# Main.net
KiCad netlist of a schematic drawn in Altium Designer
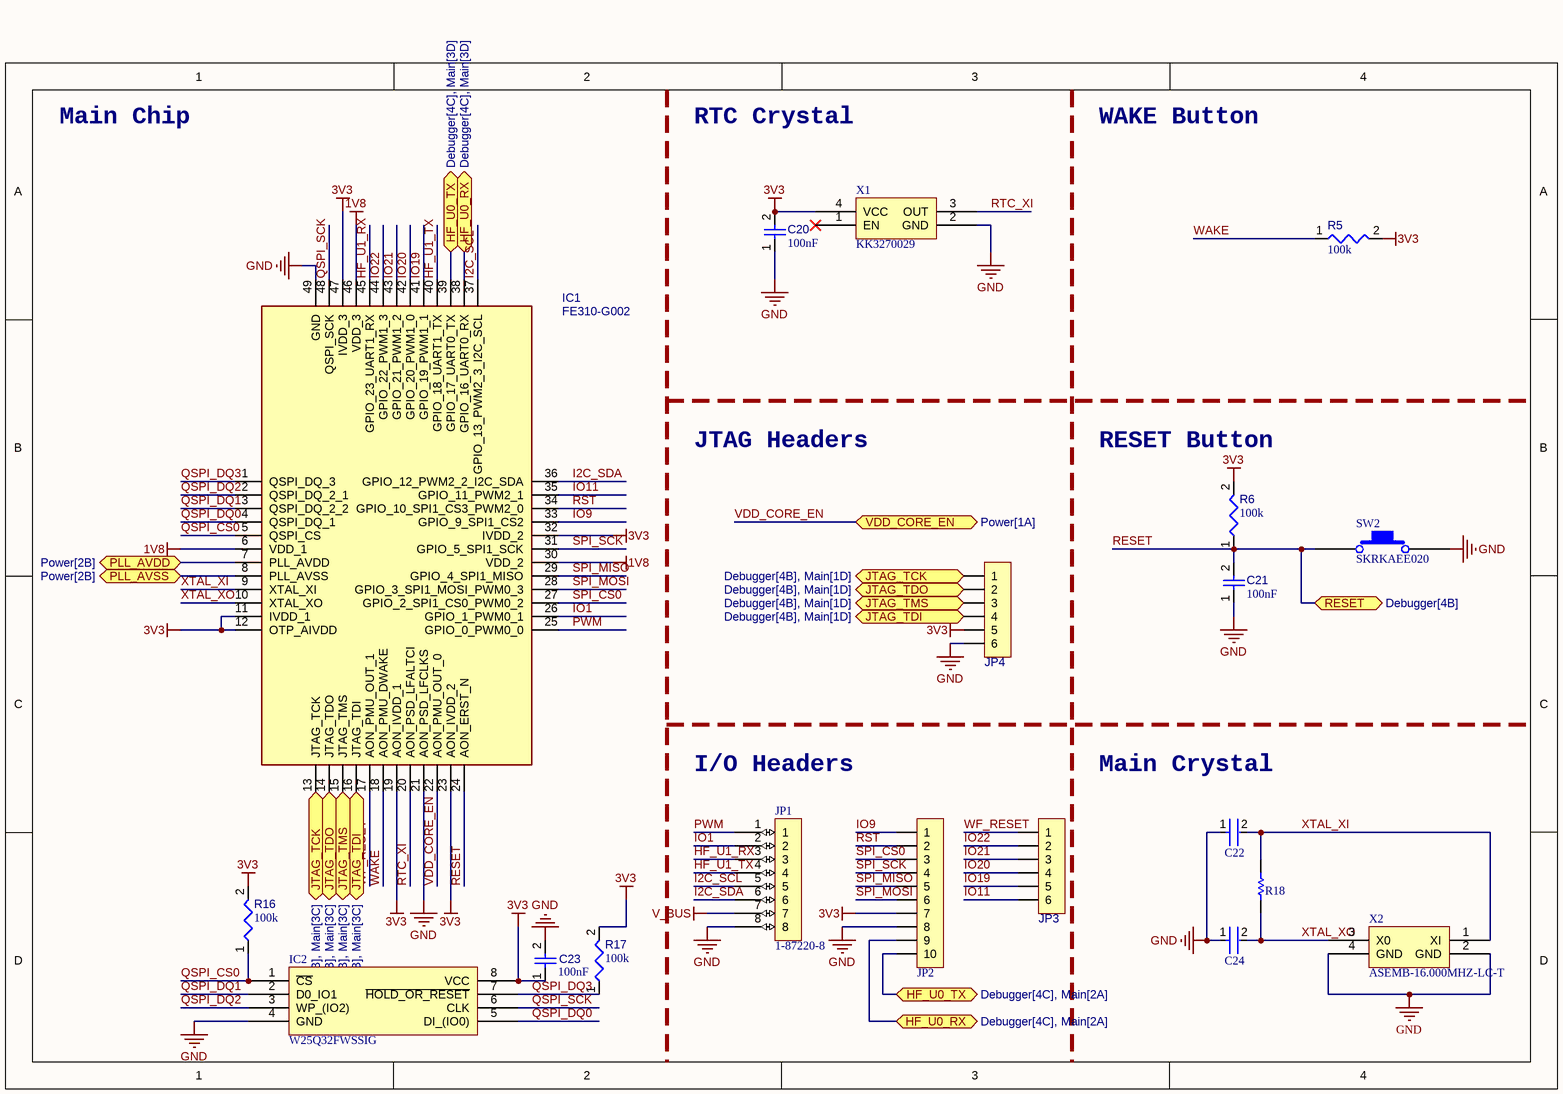
[diagram p0: Main.SchDoc]

(export (version "E")
  (design (tool "Eeschema 10.0.6"))
  (components
    (comp (ref "C20")
      (value "100nF")
      (footprint "CAPC1608X90X40NL10T20")
      (description "Chip Capacitor, 100 nF, +/- 10%, 50 V, 0603 (1608 Metric)")
      (fields (field (name "TOLERANCE") "10%") (field (name "Comment") "Capacitor 100 nF +/-10% 50 V 0603"))
      (libsource (lib "Rice University") (part "CAP-NP-2"))
    )
    (comp (ref "C21")
      (value "100nF")
      (footprint "CAPC1608X90X40NL10T20")
      (description "Chip Capacitor, 100 nF, +/- 10%, 50 V, 0603 (1608 Metric)")
      (fields (field (name "TOLERANCE") "10%") (field (name "Comment") "Capacitor 100 nF +/-10% 50 V 0603"))
      (libsource (lib "Rice University") (part "CAP-NP-2"))
    )
    (comp (ref "C22")
      (value "06035A220JAT2A")
      (footprint "FP-0603-L_1_6_0_15-W_0_81-IPC_C")
      (description "0603 22 pF 50V ±5% Tolerance C0G/NP0 Surface Mount Multilayer Ceramic Capacitor")
      (libsource (lib "Rice University") (part "02cd4be3c70576c341d710602a673aa"))
    )
    (comp (ref "C23")
      (value "100nF")
      (footprint "CAPC1608X90X40NL10T20")
      (description "Chip Capacitor, 100 nF, +/- 10%, 50 V, 0603 (1608 Metric)")
      (fields (field (name "TOLERANCE") "10%") (field (name "Comment") "Capacitor 100 nF +/-10% 50 V 0603"))
      (libsource (lib "Rice University") (part "CAP-NP-2"))
    )
    (comp (ref "C24")
      (value "06035A220JAT2A")
      (footprint "FP-0603-L_1_6_0_15-W_0_81-IPC_C")
      (description "0603 22 pF 50V ±5% Tolerance C0G/NP0 Surface Mount Multilayer Ceramic Capacitor")
      (libsource (lib "Rice University") (part "02cd4be3c70576c341d710602a673aa"))
    )
    (comp (ref "IC1")
      (value "FE310-G002")
      (footprint "SamacSys:QFN40P600X600X93-49N")
      (description "Integrated Circuit")
      (libsource (lib "*") (part "FE310-G002"))
    )
    (comp (ref "IC2")
      (value "W25Q32FWSSIG")
      (footprint "W25Q32FWSSIG-Footprint-1")
      (description "IC Flash 32M Spi 104MHZ 8SOIC / 1.8V 32M-BIT Serial Flash Memory With Dual/quad Spi & Qpi")
      (libsource (lib "Rice University") (part "W25Q32FWSSIG-Symbol-1"))
    )
    (comp (ref "JP1")
      (value "1-87220-8")
      (footprint "1-87220-8-Footprint-1")
      (description "Conn Unshrouded Header HDR 1x8 POS 2.54mm Solder ST Thru-Hole Carton")
      (libsource (lib "Rice University") (part "1-87220-8-Symbol-1"))
    )
    (comp (ref "JP2")
      (value "HDR-1X10")
      (footprint "HDR2.54-LI-10P")
      (description "10P接插件")
      (fields (field (name "版权归属") "淘宝ID:黄晶宝石"))
      (libsource (lib "5.4 - 接插件-脚距2.54 (100mil) ") (part "Header 10"))
    )
    (comp (ref "JP3")
      (value "HDR-1X6")
      (footprint "HDR2.54-M-LI-6P")
      (description "6P接插件")
      (libsource (lib "5.5 - 2.54mm连接器(KF2EDGK_XH2.54_2.54排针排母)") (part "Header 6"))
    )
    (comp (ref "JP4")
      (value "HDR-1X6")
      (footprint "HDR2.54-M-LI-6P")
      (description "6P接插件")
      (libsource (lib "5.5 - 2.54mm连接器(KF2EDGK_XH2.54_2.54排针排母)") (part "Header 6"))
    )
    (comp (ref "R5")
      (value "100k")
      (footprint "RESC1608X55X25ML10T15")
      (description "Chip Resistor, 100 KOhm, +/- 1%, 0.1 W, -55 to 155 degC, 0603 (1608 Metric)")
      (fields (field (name "TOLERANCE") "1%") (field (name "POWER") "100mW"))
      (libsource (lib "Rice University") (part "RES-2"))
    )
    (comp (ref "R6")
      (value "100k")
      (footprint "RESC1608X55X25ML10T15")
      (description "Chip Resistor, 100 KOhm, +/- 1%, 0.1 W, -55 to 155 degC, 0603 (1608 Metric)")
      (fields (field (name "TOLERANCE") "1%") (field (name "POWER") "100mW"))
      (libsource (lib "Rice University") (part "RES-2"))
    )
    (comp (ref "R16")
      (value "100k")
      (footprint "RESC1608X55X25ML10T15")
      (description "Chip Resistor, 100 KOhm, +/- 1%, 0.1 W, -55 to 155 degC, 0603 (1608 Metric)")
      (fields (field (name "TOLERANCE") "1%") (field (name "POWER") "100mW"))
      (libsource (lib "Rice University") (part "RES-2"))
    )
    (comp (ref "R17")
      (value "100k")
      (footprint "RESC1608X55X25ML10T15")
      (description "Chip Resistor, 100 KOhm, +/- 1%, 0.1 W, -55 to 155 degC, 0603 (1608 Metric)")
      (fields (field (name "TOLERANCE") "1%") (field (name "POWER") "100mW"))
      (libsource (lib "Rice University") (part "RES-2"))
    )
    (comp (ref "R18")
      (value "RC0603FR-071ML")
      (footprint "RESC1608X55X25LL10T15")
      (description "Res Thick Film 0603 1M Ohm 1% 1/10W ±100ppm/°C Molded SMD Paper T/R")
      (libsource (lib "") (part "RES-2_1"))
    )
    (comp (ref "SW2")
      (value "SKRKAEE020")
      (footprint "RESC5020X04N")
      (description "Switch Tactile N.O. SPST Round Button Gull Wing 0.05A 12VDC 1.57N SMD T/R")
      (libsource (lib "Rice University") (part "SKRKAEE020-Symbol-1"))
    )
    (comp (ref "X1")
      (value "KK3270029")
      (footprint "KK3270029-Footprint-1")
      (description "Xtal Osc Xo 32.7680KHZ Cmos SMD")
      (libsource (lib "Rice University") (part "KK3270029-Symbol-1"))
    )
    (comp (ref "X2")
      (value "ASEMB-16.000MHZ-LC-T")
      (footprint "ASEMB-16.000MHZ-LC-T-Footprint-1")
      (libsource (lib "Rice University") (part "ASEMB-16.000MHZ-LC-T-Symbol-1"))
    )
  )
  (nets
    (net (code "1") (name "/HF_U0_RX") (class "Default")
      (node (ref "IC1") (pin "38") (pinfunction "GPIO_16_UART0_RX_38") (pintype "passive"))
      (node (ref "JP2") (pin "9") (pinfunction "9_9") (pintype "passive"))
    )
    (net (code "2") (name "/HF_U0_TX") (class "Default")
      (node (ref "IC1") (pin "39") (pinfunction "GPIO_17_UART0_TX_39") (pintype "passive"))
      (node (ref "JP2") (pin "10") (pinfunction "10_10") (pintype "passive"))
    )
    (net (code "3") (name "/HF_U1_RX") (class "Default")
      (node (ref "IC1") (pin "45") (pinfunction "GPIO_23_UART1_RX_45") (pintype "passive"))
      (node (ref "JP1") (pin "3") (pinfunction "3_3") (pintype "bidirectional"))
    )
    (net (code "4") (name "/HF_U1_TX") (class "Default")
      (node (ref "IC1") (pin "40") (pinfunction "GPIO_18_UART1_TX_40") (pintype "passive"))
      (node (ref "JP1") (pin "4") (pinfunction "4_4") (pintype "bidirectional"))
    )
    (net (code "5") (name "/I2C_SCL") (class "Default")
      (node (ref "IC1") (pin "37") (pinfunction "GPIO_13_PWM2_3_I2C_SCL_37") (pintype "passive"))
      (node (ref "JP1") (pin "5") (pinfunction "5_5") (pintype "bidirectional"))
    )
    (net (code "6") (name "/I2C_SDA") (class "Default")
      (node (ref "IC1") (pin "36") (pinfunction "GPIO_12_PWM2_2_I2C_SDA_36") (pintype "passive"))
      (node (ref "JP1") (pin "6") (pinfunction "6_6") (pintype "bidirectional"))
    )
    (net (code "7") (name "/IO1") (class "Default")
      (node (ref "IC1") (pin "26") (pinfunction "GPIO_1_PWM0_1_26") (pintype "passive"))
      (node (ref "JP1") (pin "2") (pinfunction "2_2") (pintype "bidirectional"))
    )
    (net (code "8") (name "/IO9") (class "Default")
      (node (ref "IC1") (pin "33") (pinfunction "GPIO_9_SPI1_CS2_33") (pintype "passive"))
      (node (ref "JP2") (pin "1") (pinfunction "1_1") (pintype "passive"))
    )
    (net (code "9") (name "/IO11") (class "Default")
      (node (ref "IC1") (pin "35") (pinfunction "GPIO_11_PWM2_1_35") (pintype "passive"))
      (node (ref "JP3") (pin "6") (pinfunction "6_6") (pintype "passive"))
    )
    (net (code "10") (name "/IO19") (class "Default")
      (node (ref "IC1") (pin "41") (pinfunction "GPIO_19_PWM1_1_41") (pintype "passive"))
      (node (ref "JP3") (pin "5") (pinfunction "5_5") (pintype "passive"))
    )
    (net (code "11") (name "/IO20") (class "Default")
      (node (ref "IC1") (pin "42") (pinfunction "GPIO_20_PWM1_0_42") (pintype "passive"))
      (node (ref "JP3") (pin "4") (pinfunction "4_4") (pintype "passive"))
    )
    (net (code "12") (name "/IO21") (class "Default")
      (node (ref "IC1") (pin "43") (pinfunction "GPIO_21_PWM1_2_43") (pintype "passive"))
      (node (ref "JP3") (pin "3") (pinfunction "3_3") (pintype "passive"))
    )
    (net (code "13") (name "/IO22") (class "Default")
      (node (ref "IC1") (pin "44") (pinfunction "GPIO_22_PWM1_3_44") (pintype "passive"))
      (node (ref "JP3") (pin "2") (pinfunction "2_2") (pintype "passive"))
    )
    (net (code "14") (name "/JTAG_TCK") (class "Default")
      (node (ref "IC1") (pin "13") (pinfunction "JTAG_TCK_13") (pintype "passive"))
      (node (ref "JP4") (pin "1") (pinfunction "1_1") (pintype "passive"))
    )
    (net (code "15") (name "/JTAG_TDI") (class "Default")
      (node (ref "IC1") (pin "16") (pinfunction "JTAG_TDI_16") (pintype "passive"))
      (node (ref "JP4") (pin "4") (pinfunction "4_4") (pintype "passive"))
    )
    (net (code "16") (name "/JTAG_TDO") (class "Default")
      (node (ref "IC1") (pin "14") (pinfunction "JTAG_TDO_14") (pintype "passive"))
      (node (ref "JP4") (pin "2") (pinfunction "2_2") (pintype "passive"))
    )
    (net (code "17") (name "/JTAG_TMS") (class "Default")
      (node (ref "IC1") (pin "15") (pinfunction "JTAG_TMS_15") (pintype "passive"))
      (node (ref "JP4") (pin "3") (pinfunction "3_3") (pintype "passive"))
    )
    (net (code "18") (name "/PLL_AVDD") (class "Default")
      (node (ref "IC1") (pin "7") (pinfunction "PLL_AVDD_7") (pintype "passive"))
    )
    (net (code "19") (name "/PLL_AVSS") (class "Default")
      (node (ref "IC1") (pin "8") (pinfunction "PLL_AVSS_8") (pintype "passive"))
    )
    (net (code "20") (name "/PWM") (class "Default")
      (node (ref "IC1") (pin "25") (pinfunction "GPIO_0_PWM0_0_25") (pintype "passive"))
      (node (ref "JP1") (pin "1") (pinfunction "1_1") (pintype "bidirectional"))
    )
    (net (code "21") (name "/QSPI_CS0") (class "Default")
      (node (ref "IC1") (pin "5") (pinfunction "QSPI_CS_5") (pintype "passive"))
      (node (ref "IC2") (pin "1") (pinfunction "~{CS}_1") (pintype "passive"))
      (node (ref "R16") (pin "1") (pinfunction "1_1") (pintype "passive"))
    )
    (net (code "22") (name "/QSPI_DQ0") (class "Default")
      (node (ref "IC1") (pin "4") (pinfunction "QSPI_DQ_1_4") (pintype "passive"))
      (node (ref "IC2") (pin "5") (pinfunction "DI_(IO0)_5") (pintype "passive"))
    )
    (net (code "23") (name "/QSPI_DQ1") (class "Default")
      (node (ref "IC1") (pin "3") (pinfunction "QSPI_DQ_2_2_3") (pintype "passive"))
      (node (ref "IC2") (pin "2") (pinfunction "D0_IO1_2") (pintype "passive"))
    )
    (net (code "24") (name "/QSPI_DQ2") (class "Default")
      (node (ref "IC1") (pin "2") (pinfunction "QSPI_DQ_2_1_2") (pintype "passive"))
      (node (ref "IC2") (pin "3") (pinfunction "WP_(IO2)_3") (pintype "passive"))
    )
    (net (code "25") (name "/QSPI_DQ3") (class "Default")
      (node (ref "IC1") (pin "1") (pinfunction "QSPI_DQ_3_1") (pintype "passive"))
      (node (ref "IC2") (pin "7") (pinfunction "~{HOLD_OR_RESET}_7") (pintype "passive"))
      (node (ref "R17") (pin "1") (pinfunction "1_1") (pintype "passive"))
    )
    (net (code "26") (name "/QSPI_SCK") (class "Default")
      (node (ref "IC1") (pin "48") (pinfunction "QSPI_SCK_48") (pintype "passive"))
      (node (ref "IC2") (pin "6") (pinfunction "CLK_6") (pintype "passive"))
    )
    (net (code "27") (name "/RESET") (class "Default")
      (node (ref "C21") (pin "2") (pinfunction "2_2") (pintype "passive"))
      (node (ref "IC1") (pin "24") (pinfunction "AON_ERST_N_24") (pintype "passive"))
      (node (ref "R6") (pin "1") (pinfunction "1_1") (pintype "passive"))
      (node (ref "SW2") (pin "1") (pinfunction "1_1") (pintype "passive"))
    )
    (net (code "28") (name "/RST") (class "Default")
      (node (ref "IC1") (pin "34") (pinfunction "GPIO_10_SPI1_CS3_PWM2_0_34") (pintype "passive"))
      (node (ref "JP2") (pin "2") (pinfunction "2_2") (pintype "passive"))
    )
    (net (code "29") (name "/RTC_XI") (class "Default")
      (node (ref "IC1") (pin "20") (pinfunction "AON_PSD_LFALTCI_20") (pintype "passive"))
      (node (ref "X1") (pin "3") (pinfunction "OUT_3") (pintype "passive"))
    )
    (net (code "30") (name "/SPI_CS0") (class "Default")
      (node (ref "IC1") (pin "27") (pinfunction "GPIO_2_SPI1_CS0_PWM0_2_27") (pintype "passive"))
      (node (ref "JP2") (pin "3") (pinfunction "3_3") (pintype "passive"))
    )
    (net (code "31") (name "/SPI_MISO") (class "Default")
      (node (ref "IC1") (pin "29") (pinfunction "GPIO_4_SPI1_MISO_29") (pintype "passive"))
      (node (ref "JP2") (pin "5") (pinfunction "5_5") (pintype "passive"))
    )
    (net (code "32") (name "/SPI_MOSI") (class "Default")
      (node (ref "IC1") (pin "28") (pinfunction "GPIO_3_SPI1_MOSI_PWM0_3_28") (pintype "passive"))
      (node (ref "JP2") (pin "6") (pinfunction "6_6") (pintype "passive"))
    )
    (net (code "33") (name "/SPI_SCK") (class "Default")
      (node (ref "IC1") (pin "31") (pinfunction "GPIO_5_SPI1_SCK_31") (pintype "passive"))
      (node (ref "JP2") (pin "4") (pinfunction "4_4") (pintype "passive"))
    )
    (net (code "34") (name "/VDD_CORE_EN") (class "Default")
      (node (ref "IC1") (pin "22") (pinfunction "AON_PMU_OUT_0_22") (pintype "passive"))
    )
    (net (code "35") (name "/WAKE") (class "Default")
      (node (ref "IC1") (pin "18") (pinfunction "AON_PMU_DWAKE_18") (pintype "passive"))
      (node (ref "R5") (pin "1") (pinfunction "1_1") (pintype "passive"))
    )
    (net (code "36") (name "/WF_RESET") (class "Default")
      (node (ref "IC1") (pin "17") (pinfunction "AON_PMU_OUT_1_17") (pintype "passive"))
      (node (ref "JP3") (pin "1") (pinfunction "1_1") (pintype "passive"))
    )
    (net (code "37") (name "/XTAL_XI") (class "Default")
      (node (ref "C22") (pin "2") (pinfunction "2_2") (pintype "passive"))
      (node (ref "IC1") (pin "9") (pinfunction "XTAL_XI_9") (pintype "passive"))
      (node (ref "R18") (pin "2") (pinfunction "2_2") (pintype "passive"))
      (node (ref "X2") (pin "1") (pinfunction "XI_1") (pintype "passive"))
    )
    (net (code "38") (name "/XTAL_XO") (class "Default")
      (node (ref "C24") (pin "2") (pinfunction "2_2") (pintype "passive"))
      (node (ref "IC1") (pin "10") (pinfunction "XTAL_XO_10") (pintype "passive"))
      (node (ref "R18") (pin "1") (pinfunction "1_1") (pintype "passive"))
      (node (ref "X2") (pin "3") (pinfunction "X0_3") (pintype "passive"))
    )
    (net (code "39") (name "1V8") (class "Default")
      (node (ref "IC1") (pin "30") (pinfunction "VDD_2_30") (pintype "passive"))
      (node (ref "IC1") (pin "46") (pinfunction "VDD_3_46") (pintype "passive"))
      (node (ref "IC1") (pin "6") (pinfunction "VDD_1_6") (pintype "passive"))
    )
    (net (code "40") (name "3V3") (class "Default")
      (node (ref "C20") (pin "2") (pinfunction "2_2") (pintype "passive"))
      (node (ref "C23") (pin "1") (pinfunction "1_1") (pintype "passive"))
      (node (ref "IC1") (pin "11") (pinfunction "IVDD_1_11") (pintype "passive"))
      (node (ref "IC1") (pin "12") (pinfunction "OTP_AIVDD_12") (pintype "passive"))
      (node (ref "IC1") (pin "19") (pinfunction "AON_IVDD_1_19") (pintype "passive"))
      (node (ref "IC1") (pin "23") (pinfunction "AON_IVDD_2_23") (pintype "passive"))
      (node (ref "IC1") (pin "32") (pinfunction "IVDD_2_32") (pintype "passive"))
      (node (ref "IC1") (pin "47") (pinfunction "IVDD_3_47") (pintype "passive"))
      (node (ref "IC2") (pin "8") (pinfunction "VCC_8") (pintype "passive"))
      (node (ref "JP2") (pin "7") (pinfunction "7_7") (pintype "passive"))
      (node (ref "JP4") (pin "5") (pinfunction "5_5") (pintype "passive"))
      (node (ref "R16") (pin "2") (pinfunction "2_2") (pintype "passive"))
      (node (ref "R17") (pin "2") (pinfunction "2_2") (pintype "passive"))
      (node (ref "R5") (pin "2") (pinfunction "2_2") (pintype "passive"))
      (node (ref "R6") (pin "2") (pinfunction "2_2") (pintype "passive"))
      (node (ref "X1") (pin "4") (pinfunction "VCC_4") (pintype "passive"))
    )
    (net (code "41") (name "GND") (class "Default")
      (node (ref "C20") (pin "1") (pinfunction "1_1") (pintype "passive"))
      (node (ref "C21") (pin "1") (pinfunction "1_1") (pintype "passive"))
      (node (ref "C22") (pin "1") (pinfunction "1_1") (pintype "passive"))
      (node (ref "C23") (pin "2") (pinfunction "2_2") (pintype "passive"))
      (node (ref "C24") (pin "1") (pinfunction "1_1") (pintype "passive"))
      (node (ref "IC1") (pin "21") (pinfunction "AON_PSD_LFCLKS_21") (pintype "passive"))
      (node (ref "IC1") (pin "49") (pinfunction "GND_49") (pintype "passive"))
      (node (ref "IC2") (pin "4") (pinfunction "GND_4") (pintype "passive"))
      (node (ref "JP1") (pin "8") (pinfunction "8_8") (pintype "bidirectional"))
      (node (ref "JP2") (pin "8") (pinfunction "8_8") (pintype "passive"))
      (node (ref "JP4") (pin "6") (pinfunction "6_6") (pintype "passive"))
      (node (ref "SW2") (pin "2") (pinfunction "2_2") (pintype "passive"))
      (node (ref "X1") (pin "2") (pinfunction "GND_2") (pintype "passive"))
      (node (ref "X2") (pin "2") (pinfunction "GND_2") (pintype "passive"))
      (node (ref "X2") (pin "4") (pinfunction "GND_4") (pintype "passive"))
    )
    (net (code "42") (name "V_BUS") (class "Default")
      (node (ref "JP1") (pin "7") (pinfunction "7_7") (pintype "bidirectional"))
    )
    (net (code "43") (name "unconnected-(X1-EN-Pad1)") (class "Default")
      (node (ref "X1") (pin "1") (pinfunction "EN_1") (pintype "passive+no_connect"))
    )
  )
)
